# Signal_RX.net
KiCad netlist of a schematic drawn in Altium Designer
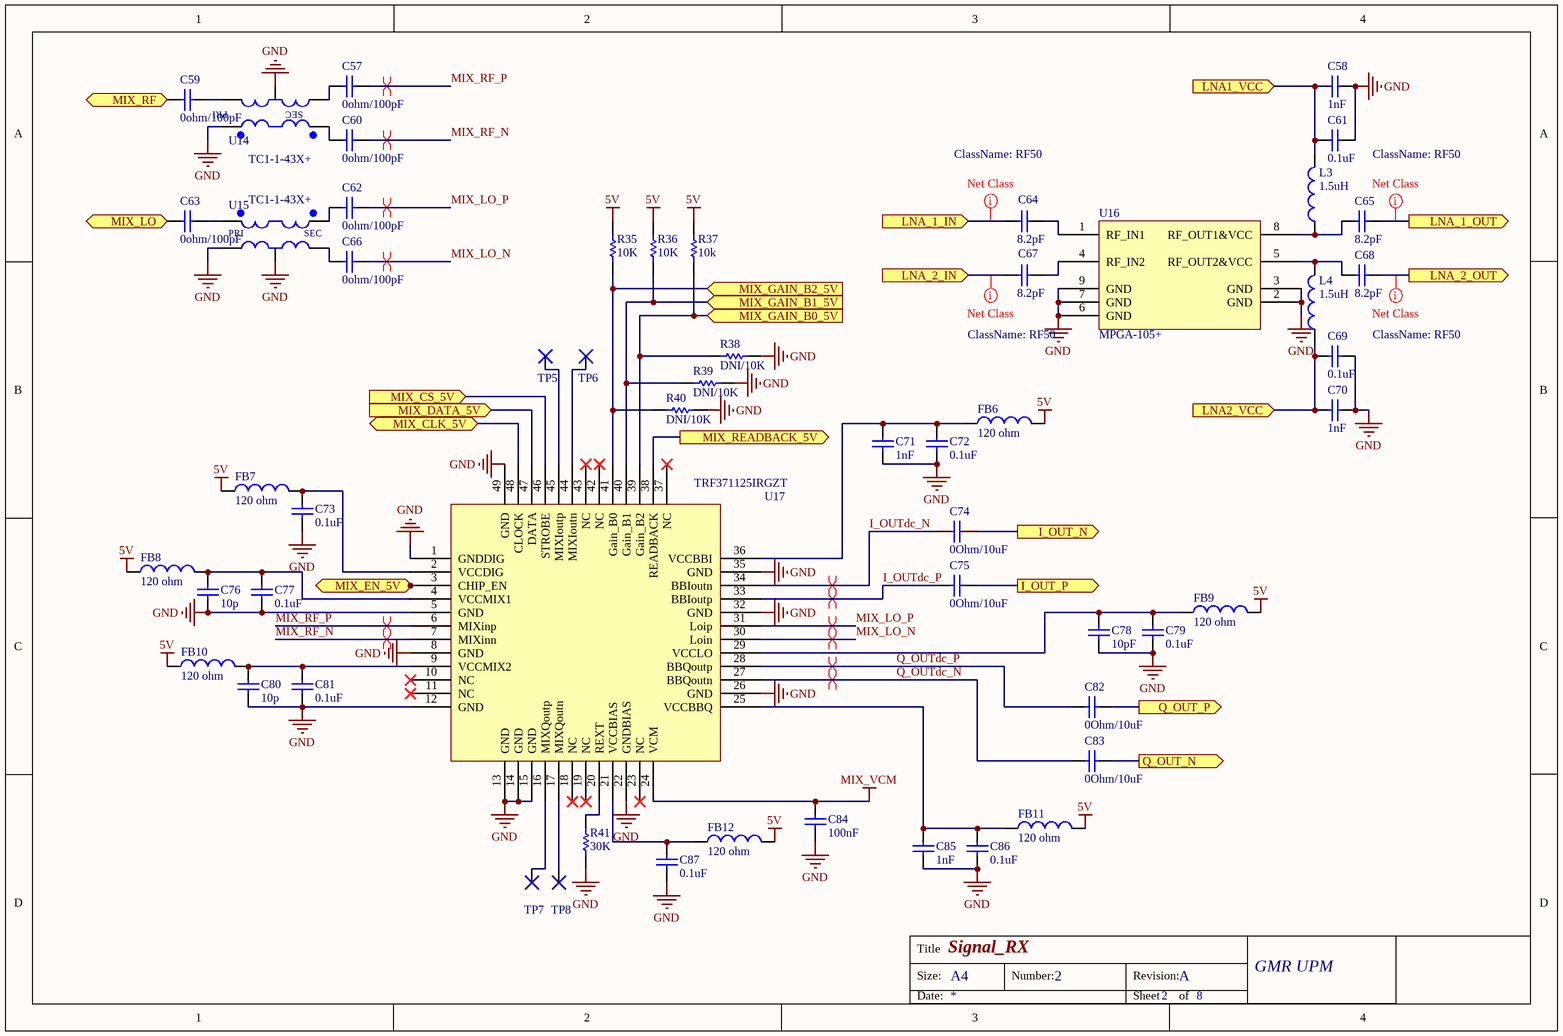
[diagram p0: Signal_RX.SchDoc]

(export (version "E")
  (design (tool "Eeschema 10.0.6"))
  (components
    (comp (ref "C57")
      (value "0ohm/100pF")
      (footprint "0603 Cap")
      (description "CAP CER 16V X7R 0603")
      (fields (field (name "TOLERANCE") "10") (field (name "VOLTAGE") "16"))
      (libsource (lib "Componentes_base") (part "C_0603"))
    )
    (comp (ref "C58")
      (value "1nF")
      (footprint "0603 Cap")
      (description "CAP CER 16V X7R 0603")
      (fields (field (name "TOLERANCE") "10") (field (name "VOLTAGE") "16"))
      (libsource (lib "Componentes_base") (part "C_0603"))
    )
    (comp (ref "C59")
      (value "0ohm/100pF")
      (footprint "0603 Cap")
      (description "CAP CER 16V X7R 0603")
      (fields (field (name "TOLERANCE") "10") (field (name "VOLTAGE") "16"))
      (libsource (lib "Componentes_base") (part "C_0603"))
    )
    (comp (ref "C60")
      (value "0ohm/100pF")
      (footprint "0603 Cap")
      (description "CAP CER 16V X7R 0603")
      (fields (field (name "TOLERANCE") "10") (field (name "VOLTAGE") "16"))
      (libsource (lib "Componentes_base") (part "C_0603"))
    )
    (comp (ref "C61")
      (value "0.1uF")
      (footprint "0603 Cap")
      (description "CAP CER 16V X7R 0603")
      (fields (field (name "TOLERANCE") "10") (field (name "VOLTAGE") "16"))
      (libsource (lib "Componentes_base") (part "C_0603"))
    )
    (comp (ref "C62")
      (value "0ohm/100pF")
      (footprint "0603 Cap")
      (description "CAP CER 16V X7R 0603")
      (fields (field (name "TOLERANCE") "10") (field (name "VOLTAGE") "16"))
      (libsource (lib "Componentes_base") (part "C_0603"))
    )
    (comp (ref "C63")
      (value "0ohm/100pF")
      (footprint "0603 Cap")
      (description "CAP CER 16V X7R 0603")
      (fields (field (name "TOLERANCE") "10") (field (name "VOLTAGE") "16"))
      (libsource (lib "Componentes_base") (part "C_0603"))
    )
    (comp (ref "C64")
      (value "8.2pF")
      (footprint "Chip2PinSM127P600-8N_CAP0402")
      (description "CAP CER 8.2PF 50V NP0 0402")
      (fields
        (field (name "MANUFACTURER") "AVX Corporation")
        (field (name "MANUFACTURER PART NUMBER") "04025A8R2BAT2A")
      )
      (libsource (lib "Componentes_base") (part "04025A8R2BAT2A"))
    )
    (comp (ref "C65")
      (value "8.2pF")
      (footprint "Chip2PinSM127P600-8N_CAP0402")
      (description "CAP CER 8.2PF 50V NP0 0402")
      (fields
        (field (name "MANUFACTURER") "AVX Corporation")
        (field (name "MANUFACTURER PART NUMBER") "04025A8R2BAT2A")
      )
      (libsource (lib "Componentes_base") (part "04025A8R2BAT2A"))
    )
    (comp (ref "C66")
      (value "0ohm/100pF")
      (footprint "0603 Cap")
      (description "CAP CER 16V X7R 0603")
      (fields (field (name "TOLERANCE") "10") (field (name "VOLTAGE") "16"))
      (libsource (lib "Componentes_base") (part "C_0603"))
    )
    (comp (ref "C67")
      (value "8.2pF")
      (footprint "Chip2PinSM127P600-8N_CAP0402")
      (description "CAP CER 8.2PF 50V NP0 0402")
      (fields
        (field (name "MANUFACTURER") "AVX Corporation")
        (field (name "MANUFACTURER PART NUMBER") "04025A8R2BAT2A")
      )
      (libsource (lib "Componentes_base") (part "04025A8R2BAT2A"))
    )
    (comp (ref "C68")
      (value "8.2pF")
      (footprint "Chip2PinSM127P600-8N_CAP0402")
      (description "CAP CER 8.2PF 50V NP0 0402")
      (fields
        (field (name "MANUFACTURER") "AVX Corporation")
        (field (name "MANUFACTURER PART NUMBER") "04025A8R2BAT2A")
      )
      (libsource (lib "Componentes_base") (part "04025A8R2BAT2A"))
    )
    (comp (ref "C69")
      (value "0.1uF")
      (footprint "0603 Cap")
      (description "CAP CER 16V X7R 0603")
      (fields (field (name "TOLERANCE") "10") (field (name "VOLTAGE") "16"))
      (libsource (lib "Componentes_base") (part "C_0603"))
    )
    (comp (ref "C70")
      (value "1nF")
      (footprint "0603 Cap")
      (description "CAP CER 16V X7R 0603")
      (fields (field (name "TOLERANCE") "10") (field (name "VOLTAGE") "16"))
      (libsource (lib "Componentes_base") (part "C_0603"))
    )
    (comp (ref "C71")
      (value "1nF")
      (footprint "0603 Cap")
      (description "CAP CER 16V X7R 0603")
      (fields (field (name "TOLERANCE") "10") (field (name "VOLTAGE") "16"))
      (libsource (lib "Componentes_base") (part "C_0603"))
    )
    (comp (ref "C72")
      (value "0.1uF")
      (footprint "0603 Cap")
      (description "CAP CER 16V X7R 0603")
      (fields (field (name "TOLERANCE") "10") (field (name "VOLTAGE") "16"))
      (libsource (lib "Componentes_base") (part "C_0603"))
    )
    (comp (ref "C73")
      (value "0.1uF")
      (footprint "0603 Cap")
      (description "CAP CER 16V X7R 0603")
      (fields (field (name "TOLERANCE") "10") (field (name "VOLTAGE") "16"))
      (libsource (lib "Componentes_base") (part "C_0603"))
    )
    (comp (ref "C74")
      (value "0Ohm/10uF")
      (footprint "0603 Cap")
      (description "CAP CER 16V X7R 0603")
      (fields (field (name "TOLERANCE") "10") (field (name "VOLTAGE") "16"))
      (libsource (lib "Componentes_base") (part "C_0603"))
    )
    (comp (ref "C75")
      (value "0Ohm/10uF")
      (footprint "0603 Cap")
      (description "CAP CER 16V X7R 0603")
      (fields (field (name "TOLERANCE") "10") (field (name "VOLTAGE") "16"))
      (libsource (lib "Componentes_base") (part "C_0603"))
    )
    (comp (ref "C76")
      (value "10p")
      (footprint "0603 Cap")
      (description "CAP CER 16V X7R 0603")
      (fields (field (name "TOLERANCE") "10") (field (name "VOLTAGE") "16"))
      (libsource (lib "Componentes_base") (part "C_0603"))
    )
    (comp (ref "C77")
      (value "0.1uF")
      (footprint "0603 Cap")
      (description "CAP CER 16V X7R 0603")
      (fields (field (name "TOLERANCE") "10") (field (name "VOLTAGE") "16"))
      (libsource (lib "Componentes_base") (part "C_0603"))
    )
    (comp (ref "C78")
      (value "10pF")
      (footprint "0603 Cap")
      (description "CAP CER 16V X7R 0603")
      (fields (field (name "TOLERANCE") "10") (field (name "VOLTAGE") "16"))
      (libsource (lib "Componentes_base") (part "C_0603"))
    )
    (comp (ref "C79")
      (value "0.1uF")
      (footprint "0603 Cap")
      (description "CAP CER 16V X7R 0603")
      (fields (field (name "TOLERANCE") "10") (field (name "VOLTAGE") "16"))
      (libsource (lib "Componentes_base") (part "C_0603"))
    )
    (comp (ref "C80")
      (value "10p")
      (footprint "0603 Cap")
      (description "CAP CER 16V X7R 0603")
      (fields (field (name "TOLERANCE") "10") (field (name "VOLTAGE") "16"))
      (libsource (lib "Componentes_base") (part "C_0603"))
    )
    (comp (ref "C81")
      (value "0.1uF")
      (footprint "0603 Cap")
      (description "CAP CER 16V X7R 0603")
      (fields (field (name "TOLERANCE") "10") (field (name "VOLTAGE") "16"))
      (libsource (lib "Componentes_base") (part "C_0603"))
    )
    (comp (ref "C82")
      (value "0Ohm/10uF")
      (footprint "0603 Cap")
      (description "CAP CER 16V X7R 0603")
      (fields (field (name "TOLERANCE") "10") (field (name "VOLTAGE") "16"))
      (libsource (lib "Componentes_base") (part "C_0603"))
    )
    (comp (ref "C83")
      (value "0Ohm/10uF")
      (footprint "0603 Cap")
      (description "CAP CER 16V X7R 0603")
      (fields (field (name "TOLERANCE") "10") (field (name "VOLTAGE") "16"))
      (libsource (lib "Componentes_base") (part "C_0603"))
    )
    (comp (ref "C84")
      (value "100nF")
      (footprint "0603 Cap")
      (description "CAP CER 16V X7R 0603")
      (fields (field (name "TOLERANCE") "10") (field (name "VOLTAGE") "16"))
      (libsource (lib "Componentes_base") (part "C_0603"))
    )
    (comp (ref "C85")
      (value "1nF")
      (footprint "0603 Cap")
      (description "CAP CER 16V X7R 0603")
      (fields (field (name "TOLERANCE") "10") (field (name "VOLTAGE") "16"))
      (libsource (lib "Componentes_base") (part "C_0603"))
    )
    (comp (ref "C86")
      (value "0.1uF")
      (footprint "0603 Cap")
      (description "CAP CER 16V X7R 0603")
      (fields (field (name "TOLERANCE") "10") (field (name "VOLTAGE") "16"))
      (libsource (lib "Componentes_base") (part "C_0603"))
    )
    (comp (ref "C87")
      (value "0.1uF")
      (footprint "0603 Cap")
      (description "CAP CER 16V X7R 0603")
      (fields (field (name "TOLERANCE") "10") (field (name "VOLTAGE") "16"))
      (libsource (lib "Componentes_base") (part "C_0603"))
    )
    (comp (ref "FB6")
      (value "120 ohm")
      (footprint "INDC1608X08L")
      (description "FERRITE BEAD 120 OHM 0603 1LN")
      (fields
        (field (name "MANUFACTURER") "Murata Electronics North America")
        (field (name "MANUFACTURER PART NUMBER") "BLM18PG121SN1D")
      )
      (libsource (lib "Componentes_base") (part "BLM18PG121SN1D"))
    )
    (comp (ref "FB7")
      (value "120 ohm")
      (footprint "INDC1608X08L")
      (description "FERRITE BEAD 120 OHM 0603 1LN")
      (fields
        (field (name "MANUFACTURER") "Murata Electronics North America")
        (field (name "MANUFACTURER PART NUMBER") "BLM18PG121SN1D")
      )
      (libsource (lib "") (part "BLM18PG121SN1D_1"))
    )
    (comp (ref "FB8")
      (value "120 ohm")
      (footprint "INDC1608X08L")
      (description "FERRITE BEAD 120 OHM 0603 1LN")
      (fields
        (field (name "MANUFACTURER") "Murata Electronics North America")
        (field (name "MANUFACTURER PART NUMBER") "BLM18PG121SN1D")
      )
      (libsource (lib "") (part "BLM18PG121SN1D_1"))
    )
    (comp (ref "FB9")
      (value "120 ohm")
      (footprint "INDC1608X08L")
      (description "FERRITE BEAD 120 OHM 0603 1LN")
      (fields
        (field (name "MANUFACTURER") "Murata Electronics North America")
        (field (name "MANUFACTURER PART NUMBER") "BLM18PG121SN1D")
      )
      (libsource (lib "Componentes_base") (part "BLM18PG121SN1D"))
    )
    (comp (ref "FB10")
      (value "120 ohm")
      (footprint "INDC1608X08L")
      (description "FERRITE BEAD 120 OHM 0603 1LN")
      (fields
        (field (name "MANUFACTURER") "Murata Electronics North America")
        (field (name "MANUFACTURER PART NUMBER") "BLM18PG121SN1D")
      )
      (libsource (lib "") (part "BLM18PG121SN1D_1"))
    )
    (comp (ref "FB11")
      (value "120 ohm")
      (footprint "INDC1608X08L")
      (description "FERRITE BEAD 120 OHM 0603 1LN")
      (fields
        (field (name "MANUFACTURER") "Murata Electronics North America")
        (field (name "MANUFACTURER PART NUMBER") "BLM18PG121SN1D")
      )
      (libsource (lib "Componentes_base") (part "BLM18PG121SN1D"))
    )
    (comp (ref "FB12")
      (value "120 ohm")
      (footprint "INDC1608X08L")
      (description "FERRITE BEAD 120 OHM 0603 1LN")
      (fields
        (field (name "MANUFACTURER") "Murata Electronics North America")
        (field (name "MANUFACTURER PART NUMBER") "BLM18PG121SN1D")
      )
      (libsource (lib "Componentes_base") (part "BLM18PG121SN1D"))
    )
    (comp (ref "L3")
      (value "1.5uH")
      (footprint "INDC1008X07L")
      (description "FIXED IND 1.5UH 630MA 760 MOHM")
      (fields
        (field (name "MANUFACTURER") "Abracon LLC")
        (field (name "MANUFACTURER PART NUMBER") "AISC-1008F-1R5G-T")
      )
      (libsource (lib "") (part "AISC-1008F-1R5G-T_1"))
    )
    (comp (ref "L4")
      (value "1.5uH")
      (footprint "INDC1008X07L")
      (description "FIXED IND 1.5UH 630MA 760 MOHM")
      (fields
        (field (name "MANUFACTURER") "Abracon LLC")
        (field (name "MANUFACTURER PART NUMBER") "AISC-1008F-1R5G-T")
      )
      (libsource (lib "Componentes_base") (part "AISC-1008F-1R5G-T"))
    )
    (comp (ref "R35")
      (value "10K")
      (footprint "0603 Res")
      (description "SMD Resistor, 1%, 0.1W, 0603")
      (fields (field (name "TOLERANCE") "1"))
      (libsource (lib "Componentes_base") (part "R_0603"))
    )
    (comp (ref "R36")
      (value "10K")
      (footprint "0603 Res")
      (description "SMD Resistor, 1%, 0.1W, 0603")
      (fields (field (name "TOLERANCE") "1"))
      (libsource (lib "Componentes_base") (part "R_0603"))
    )
    (comp (ref "R37")
      (value "10k")
      (footprint "0603 Res")
      (description "SMD Resistor, 1%, 0.1W, 0603")
      (fields (field (name "TOLERANCE") "1"))
      (libsource (lib "Componentes_base") (part "R_0603"))
    )
    (comp (ref "R38")
      (value "DNI/10K")
      (footprint "0603 Res")
      (description "SMD Resistor, 1%, 0.1W, 0603")
      (fields (field (name "TOLERANCE") "1"))
      (libsource (lib "Componentes_base") (part "R_0603"))
    )
    (comp (ref "R39")
      (value "DNI/10K")
      (footprint "0603 Res")
      (description "SMD Resistor, 1%, 0.1W, 0603")
      (fields (field (name "TOLERANCE") "1"))
      (libsource (lib "Componentes_base") (part "R_0603"))
    )
    (comp (ref "R40")
      (value "DNI/10K")
      (footprint "0603 Res")
      (description "SMD Resistor, 1%, 0.1W, 0603")
      (fields (field (name "TOLERANCE") "1"))
      (libsource (lib "Componentes_base") (part "R_0603"))
    )
    (comp (ref "R41")
      (value "30K")
      (footprint "0603 Res")
      (description "SMD Resistor, 1%, 0.1W, 0603")
      (fields (field (name "TOLERANCE") "1"))
      (libsource (lib "Componentes_base") (part "R_0603"))
    )
    (comp (ref "TP5")
      (value "TEST_POINT_PIN")
      (footprint "TESTPOINT")
      (description "Test point for single pin")
      (libsource (lib "Componentes_base") (part "TEST_POINT_PIN"))
    )
    (comp (ref "TP6")
      (value "TEST_POINT_PIN")
      (footprint "TESTPOINT")
      (description "Test point for single pin")
      (libsource (lib "Componentes_base") (part "TEST_POINT_PIN"))
    )
    (comp (ref "TP7")
      (value "TEST_POINT_PIN")
      (footprint "TESTPOINT")
      (description "Test point for single pin")
      (libsource (lib "Componentes_base") (part "TEST_POINT_PIN"))
    )
    (comp (ref "TP8")
      (value "TEST_POINT_PIN")
      (footprint "TESTPOINT")
      (description "Test point for single pin")
      (libsource (lib "Componentes_base") (part "TEST_POINT_PIN"))
    )
    (comp (ref "U14")
      (value "TC1-1-43X+")
      (footprint "AT1521")
      (description "SMD RF Transformer")
      (fields (field (name "MANUFACTURER") "Minicircuits"))
      (libsource (lib "") (part "TC1-1-43X+_1"))
    )
    (comp (ref "U15")
      (value "TC1-1-43X+")
      (footprint "AT1521")
      (description "SMD RF Transformer")
      (fields (field (name "MANUFACTURER") "Minicircuits"))
      (libsource (lib "Schlib1") (part "TC1-1-43X+"))
    )
    (comp (ref "U16")
      (value "MPGA-105+")
      (footprint "DL1020_recomendedValues")
      (description "Dual Matched MMIC Ampli er")
      (fields (field (name "MANUFACTURER") "Minicircuits"))
      (libsource (lib "Schlib1") (part "MPGA-105+"))
    )
    (comp (ref "U17")
      (value "TRF371125IRGZT")
      (footprint "QFN50P700X700X100_HS-49M")
      (description "IC IQ DEMODULATOR W/PGA 48VQFN")
      (fields (field (name "MANUFACTURER") "Texas Instruments"))
      (libsource (lib "Schlib1") (part "TRF371125IRGZT"))
    )
  )
  (nets
    (net (code "1") (name "/I_OUT_N") (class "Default")
      (node (ref "C74") (pin "1") (pinfunction "1_1") (pintype "passive"))
    )
    (net (code "2") (name "/I_OUT_P") (class "Default")
      (node (ref "C75") (pin "1") (pinfunction "1_1") (pintype "passive"))
    )
    (net (code "3") (name "/I_OUTdc_N") (class "Default")
      (node (ref "C74") (pin "2") (pinfunction "2_2") (pintype "passive"))
      (node (ref "U17") (pin "34") (pinfunction "BBIoutn_34") (pintype "passive"))
    )
    (net (code "4") (name "/I_OUTdc_P") (class "Default")
      (node (ref "C75") (pin "2") (pinfunction "2_2") (pintype "passive"))
      (node (ref "U17") (pin "33") (pinfunction "BBIoutp_33") (pintype "passive"))
    )
    (net (code "5") (name "/LNA1_VCC") (class "Default")
      (node (ref "C58") (pin "2") (pinfunction "2_2") (pintype "passive"))
      (node (ref "C61") (pin "2") (pinfunction "2_2") (pintype "passive"))
      (node (ref "L3") (pin "2") (pinfunction "2_2") (pintype "passive"))
    )
    (net (code "6") (name "/LNA2_VCC") (class "Default")
      (node (ref "C69") (pin "1") (pinfunction "1_1") (pintype "passive"))
      (node (ref "C70") (pin "1") (pinfunction "1_1") (pintype "passive"))
      (node (ref "L4") (pin "2") (pinfunction "2_2") (pintype "passive"))
    )
    (net (code "7") (name "/LNA_1_IN") (class "Default")
      (node (ref "C64") (pin "1") (pinfunction "1_1") (pintype "passive"))
    )
    (net (code "8") (name "/LNA_1_OUT") (class "Default")
      (node (ref "C65") (pin "2") (pinfunction "2_2") (pintype "passive"))
    )
    (net (code "9") (name "/LNA_2_IN") (class "Default")
      (node (ref "C67") (pin "1") (pinfunction "1_1") (pintype "passive"))
    )
    (net (code "10") (name "/LNA_2_OUT") (class "Default")
      (node (ref "C68") (pin "2") (pinfunction "2_2") (pintype "passive"))
    )
    (net (code "11") (name "/MIX_CLK_5V") (class "Default")
      (node (ref "U17") (pin "48") (pinfunction "CLOCK_48") (pintype "passive"))
    )
    (net (code "12") (name "/MIX_CS_5V") (class "Default")
      (node (ref "U17") (pin "46") (pinfunction "STROBE_46") (pintype "passive"))
    )
    (net (code "13") (name "/MIX_DATA_5V") (class "Default")
      (node (ref "U17") (pin "47") (pinfunction "DATA_47") (pintype "passive"))
    )
    (net (code "15") (name "/MIX_GAIN_B0_5V") (class "Default")
      (node (ref "R37") (pin "1") (pinfunction "1_1") (pintype "passive"))
      (node (ref "R38") (pin "2") (pinfunction "2_2") (pintype "passive"))
      (node (ref "U17") (pin "39") (pinfunction "Gain_B2_39") (pintype "passive"))
    )
    (net (code "16") (name "/MIX_GAIN_B1_5V") (class "Default")
      (node (ref "R36") (pin "1") (pinfunction "1_1") (pintype "passive"))
      (node (ref "R39") (pin "2") (pinfunction "2_2") (pintype "passive"))
      (node (ref "U17") (pin "40") (pinfunction "Gain_B1_40") (pintype "passive"))
    )
    (net (code "17") (name "/MIX_GAIN_B2_5V") (class "Default")
      (node (ref "R35") (pin "1") (pinfunction "1_1") (pintype "passive"))
      (node (ref "R40") (pin "2") (pinfunction "2_2") (pintype "passive"))
      (node (ref "U17") (pin "41") (pinfunction "Gain_B0_41") (pintype "passive"))
    )
    (net (code "18") (name "/MIX_LO") (class "Default")
      (node (ref "C63") (pin "1") (pinfunction "1_1") (pintype "passive"))
    )
    (net (code "19") (name "/MIX_LO_N") (class "Default")
      (node (ref "C66") (pin "2") (pinfunction "2_2") (pintype "passive"))
      (node (ref "U17") (pin "30") (pinfunction "Loin_30") (pintype "passive"))
    )
    (net (code "20") (name "/MIX_LO_P") (class "Default")
      (node (ref "C62") (pin "2") (pinfunction "2_2") (pintype "passive"))
      (node (ref "U17") (pin "31") (pinfunction "Loip_31") (pintype "passive"))
    )
    (net (code "21") (name "/MIX_READBACK_5V") (class "Default")
      (node (ref "U17") (pin "38") (pinfunction "READBACK_38") (pintype "passive"))
    )
    (net (code "22") (name "/MIX_RF") (class "Default")
      (node (ref "C59") (pin "1") (pinfunction "1_1") (pintype "passive"))
    )
    (net (code "23") (name "/MIX_RF_N") (class "Default")
      (node (ref "C60") (pin "2") (pinfunction "2_2") (pintype "passive"))
      (node (ref "U17") (pin "7") (pinfunction "MIXinn_7") (pintype "passive"))
    )
    (net (code "24") (name "/MIX_RF_P") (class "Default")
      (node (ref "C57") (pin "2") (pinfunction "2_2") (pintype "passive"))
      (node (ref "U17") (pin "6") (pinfunction "MIXinp_6") (pintype "passive"))
    )
    (net (code "25") (name "/Q_OUT_N") (class "Default")
      (node (ref "C83") (pin "1") (pinfunction "1_1") (pintype "passive"))
    )
    (net (code "26") (name "/Q_OUT_P") (class "Default")
      (node (ref "C82") (pin "1") (pinfunction "1_1") (pintype "passive"))
    )
    (net (code "27") (name "/Q_OUTdc_N") (class "Default")
      (node (ref "C83") (pin "2") (pinfunction "2_2") (pintype "passive"))
      (node (ref "U17") (pin "27") (pinfunction "BBQoutn_27") (pintype "passive"))
    )
    (net (code "28") (name "/Q_OUTdc_P") (class "Default")
      (node (ref "C82") (pin "2") (pinfunction "2_2") (pintype "passive"))
      (node (ref "U17") (pin "28") (pinfunction "BBQoutp_28") (pintype "passive"))
    )
    (net (code "29") (name "5V") (class "Default")
      (node (ref "FB10") (pin "1") (pinfunction "1_1") (pintype "passive"))
      (node (ref "FB11") (pin "1") (pinfunction "1_1") (pintype "passive"))
      (node (ref "FB12") (pin "1") (pinfunction "1_1") (pintype "passive"))
      (node (ref "FB6") (pin "1") (pinfunction "1_1") (pintype "passive"))
      (node (ref "FB7") (pin "1") (pinfunction "1_1") (pintype "passive"))
      (node (ref "FB8") (pin "1") (pinfunction "1_1") (pintype "passive"))
      (node (ref "FB9") (pin "1") (pinfunction "1_1") (pintype "passive"))
      (node (ref "R35") (pin "2") (pinfunction "2_2") (pintype "passive"))
      (node (ref "R36") (pin "2") (pinfunction "2_2") (pintype "passive"))
      (node (ref "R37") (pin "2") (pinfunction "2_2") (pintype "passive"))
    )
    (net (code "30") (name "GND") (class "Default")
      (node (ref "C58") (pin "1") (pinfunction "1_1") (pintype "passive"))
      (node (ref "C61") (pin "1") (pinfunction "1_1") (pintype "passive"))
      (node (ref "C69") (pin "2") (pinfunction "2_2") (pintype "passive"))
      (node (ref "C70") (pin "2") (pinfunction "2_2") (pintype "passive"))
      (node (ref "C71") (pin "2") (pinfunction "2_2") (pintype "passive"))
      (node (ref "C72") (pin "2") (pinfunction "2_2") (pintype "passive"))
      (node (ref "C73") (pin "1") (pinfunction "1_1") (pintype "passive"))
      (node (ref "C76") (pin "1") (pinfunction "1_1") (pintype "passive"))
      (node (ref "C77") (pin "1") (pinfunction "1_1") (pintype "passive"))
      (node (ref "C78") (pin "2") (pinfunction "2_2") (pintype "passive"))
      (node (ref "C79") (pin "2") (pinfunction "2_2") (pintype "passive"))
      (node (ref "C80") (pin "1") (pinfunction "1_1") (pintype "passive"))
      (node (ref "C81") (pin "1") (pinfunction "1_1") (pintype "passive"))
      (node (ref "C84") (pin "2") (pinfunction "2_2") (pintype "passive"))
      (node (ref "C85") (pin "2") (pinfunction "2_2") (pintype "passive"))
      (node (ref "C86") (pin "2") (pinfunction "2_2") (pintype "passive"))
      (node (ref "C87") (pin "2") (pinfunction "2_2") (pintype "passive"))
      (node (ref "R38") (pin "1") (pinfunction "1_1") (pintype "passive"))
      (node (ref "R39") (pin "1") (pinfunction "1_1") (pintype "passive"))
      (node (ref "R40") (pin "1") (pinfunction "1_1") (pintype "passive"))
      (node (ref "R41") (pin "1") (pinfunction "1_1") (pintype "passive"))
      (node (ref "U14") (pin "2") (pinfunction "NC_2") (pintype "passive"))
      (node (ref "U14") (pin "6") (pinfunction "6_6") (pintype "passive"))
      (node (ref "U15") (pin "2") (pinfunction "NC_2") (pintype "passive"))
      (node (ref "U15") (pin "4") (pinfunction "4_4") (pintype "passive"))
      (node (ref "U16") (pin "2") (pinfunction "GND_2") (pintype "power_in"))
      (node (ref "U16") (pin "3") (pinfunction "GND_3") (pintype "power_in"))
      (node (ref "U16") (pin "6") (pinfunction "GND_6") (pintype "power_in"))
      (node (ref "U16") (pin "7") (pinfunction "GND_7") (pintype "power_in"))
      (node (ref "U16") (pin "9") (pinfunction "GND_9") (pintype "power_in"))
      (node (ref "U17") (pin "1") (pinfunction "GNDDIG_1") (pintype "power_in"))
      (node (ref "U17") (pin "12") (pinfunction "GND_12") (pintype "power_in"))
      (node (ref "U17") (pin "13") (pinfunction "GND_13") (pintype "power_in"))
      (node (ref "U17") (pin "14") (pinfunction "GND_14") (pintype "power_in"))
      (node (ref "U17") (pin "15") (pinfunction "GND_15") (pintype "power_in"))
      (node (ref "U17") (pin "22") (pinfunction "GNDBIAS_22") (pintype "power_in"))
      (node (ref "U17") (pin "26") (pinfunction "GND_26") (pintype "power_in"))
      (node (ref "U17") (pin "32") (pinfunction "GND_32") (pintype "power_in"))
      (node (ref "U17") (pin "35") (pinfunction "GND_35") (pintype "power_in"))
      (node (ref "U17") (pin "49") (pinfunction "GND_49") (pintype "power_in"))
      (node (ref "U17") (pin "5") (pinfunction "GND_5") (pintype "power_in"))
      (node (ref "U17") (pin "8") (pinfunction "GND_8") (pintype "power_in"))
    )
    (net (code "31") (name "MIX_VCM") (class "Default")
      (node (ref "C84") (pin "1") (pinfunction "1_1") (pintype "passive"))
      (node (ref "U17") (pin "24") (pinfunction "VCM_24") (pintype "passive"))
    )
    (net (code "32") (name "Net-(C57-Pad1)") (class "Default")
      (node (ref "C57") (pin "1") (pinfunction "1_1") (pintype "passive"))
      (node (ref "U14") (pin "3") (pinfunction "3_3") (pintype "passive"))
    )
    (net (code "33") (name "Net-(C59-Pad2)") (class "Default")
      (node (ref "C59") (pin "2") (pinfunction "2_2") (pintype "passive"))
      (node (ref "U14") (pin "4") (pinfunction "4_4") (pintype "passive"))
    )
    (net (code "34") (name "Net-(C60-Pad1)") (class "Default")
      (node (ref "C60") (pin "1") (pinfunction "1_1") (pintype "passive"))
      (node (ref "U14") (pin "1") (pinfunction "1_1") (pintype "passive"))
    )
    (net (code "35") (name "Net-(C62-Pad1)") (class "Default")
      (node (ref "C62") (pin "1") (pinfunction "1_1") (pintype "passive"))
      (node (ref "U15") (pin "1") (pinfunction "1_1") (pintype "passive"))
    )
    (net (code "36") (name "Net-(C63-Pad2)") (class "Default")
      (node (ref "C63") (pin "2") (pinfunction "2_2") (pintype "passive"))
      (node (ref "U15") (pin "6") (pinfunction "6_6") (pintype "passive"))
    )
    (net (code "37") (name "Net-(C66-Pad1)") (class "Default")
      (node (ref "C66") (pin "1") (pinfunction "1_1") (pintype "passive"))
      (node (ref "U15") (pin "3") (pinfunction "3_3") (pintype "passive"))
    )
    (net (code "38") (name "Net-(U16-RF_IN1)") (class "Default")
      (node (ref "C64") (pin "2") (pinfunction "2_2") (pintype "passive"))
      (node (ref "U16") (pin "1") (pinfunction "RF_IN1_1") (pintype "passive"))
    )
    (net (code "39") (name "Net-(U16-RF_IN2)") (class "Default")
      (node (ref "C67") (pin "2") (pinfunction "2_2") (pintype "passive"))
      (node (ref "U16") (pin "4") (pinfunction "RF_IN2_4") (pintype "passive"))
    )
    (net (code "40") (name "Net-(U16-RF_OUT1&VCC)") (class "Default")
      (node (ref "C65") (pin "1") (pinfunction "1_1") (pintype "passive"))
      (node (ref "L3") (pin "1") (pinfunction "1_1") (pintype "passive"))
      (node (ref "U16") (pin "8") (pinfunction "RF_OUT1&VCC_8") (pintype "passive"))
    )
    (net (code "41") (name "Net-(U16-RF_OUT2&VCC)") (class "Default")
      (node (ref "C68") (pin "1") (pinfunction "1_1") (pintype "passive"))
      (node (ref "L4") (pin "1") (pinfunction "1_1") (pintype "passive"))
      (node (ref "U16") (pin "5") (pinfunction "RF_OUT2&VCC_5") (pintype "passive"))
    )
    (net (code "42") (name "Net-(U17-MIXIoutn)") (class "Default")
      (node (ref "TP6") (pin "1") (pinfunction "1_1") (pintype "passive"))
      (node (ref "U17") (pin "44") (pinfunction "MIXIoutn_44") (pintype "passive"))
    )
    (net (code "43") (name "Net-(U17-MIXIoutp)") (class "Default")
      (node (ref "TP5") (pin "1") (pinfunction "1_1") (pintype "passive"))
      (node (ref "U17") (pin "45") (pinfunction "MIXIoutp_45") (pintype "passive"))
    )
    (net (code "44") (name "Net-(U17-MIXQoutn)") (class "Default")
      (node (ref "TP8") (pin "1") (pinfunction "1_1") (pintype "passive"))
      (node (ref "U17") (pin "17") (pinfunction "MIXQoutn_17") (pintype "passive"))
    )
    (net (code "45") (name "Net-(U17-MIXQoutp)") (class "Default")
      (node (ref "TP7") (pin "1") (pinfunction "1_1") (pintype "passive"))
      (node (ref "U17") (pin "16") (pinfunction "MIXQoutp_16") (pintype "passive"))
    )
    (net (code "46") (name "Net-(U17-REXT)") (class "Default")
      (node (ref "R41") (pin "2") (pinfunction "2_2") (pintype "passive"))
      (node (ref "U17") (pin "20") (pinfunction "REXT_20") (pintype "passive"))
    )
    (net (code "47") (name "Net-(U17-VCCBBI)") (class "Default")
      (node (ref "C71") (pin "1") (pinfunction "1_1") (pintype "passive"))
      (node (ref "C72") (pin "1") (pinfunction "1_1") (pintype "passive"))
      (node (ref "FB6") (pin "2") (pinfunction "2_2") (pintype "passive"))
      (node (ref "U17") (pin "36") (pinfunction "VCCBBI_36") (pintype "power_in"))
    )
    (net (code "48") (name "Net-(U17-VCCBBQ)") (class "Default")
      (node (ref "C85") (pin "1") (pinfunction "1_1") (pintype "passive"))
      (node (ref "C86") (pin "1") (pinfunction "1_1") (pintype "passive"))
      (node (ref "FB11") (pin "2") (pinfunction "2_2") (pintype "passive"))
      (node (ref "U17") (pin "25") (pinfunction "VCCBBQ_25") (pintype "power_in"))
    )
    (net (code "49") (name "Net-(U17-VCCBIAS)") (class "Default")
      (node (ref "C87") (pin "1") (pinfunction "1_1") (pintype "passive"))
      (node (ref "FB12") (pin "2") (pinfunction "2_2") (pintype "passive"))
      (node (ref "U17") (pin "21") (pinfunction "VCCBIAS_21") (pintype "power_in"))
    )
    (net (code "50") (name "Net-(U17-VCCDIG)") (class "Default")
      (node (ref "C73") (pin "2") (pinfunction "2_2") (pintype "passive"))
      (node (ref "FB7") (pin "2") (pinfunction "2_2") (pintype "passive"))
      (node (ref "U17") (pin "2") (pinfunction "VCCDIG_2") (pintype "power_in"))
    )
    (net (code "51") (name "Net-(U17-VCCLO)") (class "Default")
      (node (ref "C78") (pin "1") (pinfunction "1_1") (pintype "passive"))
      (node (ref "C79") (pin "1") (pinfunction "1_1") (pintype "passive"))
      (node (ref "FB9") (pin "2") (pinfunction "2_2") (pintype "passive"))
      (node (ref "U17") (pin "29") (pinfunction "VCCLO_29") (pintype "power_in"))
    )
    (net (code "52") (name "Net-(U17-VCCMIX1)") (class "Default")
      (node (ref "C76") (pin "2") (pinfunction "2_2") (pintype "passive"))
      (node (ref "C77") (pin "2") (pinfunction "2_2") (pintype "passive"))
      (node (ref "FB8") (pin "2") (pinfunction "2_2") (pintype "passive"))
      (node (ref "U17") (pin "4") (pinfunction "VCCMIX1_4") (pintype "power_in"))
    )
    (net (code "53") (name "Net-(U17-VCCMIX2)") (class "Default")
      (node (ref "C80") (pin "2") (pinfunction "2_2") (pintype "passive"))
      (node (ref "C81") (pin "2") (pinfunction "2_2") (pintype "passive"))
      (node (ref "FB10") (pin "2") (pinfunction "2_2") (pintype "passive"))
      (node (ref "U17") (pin "9") (pinfunction "VCCMIX2_9") (pintype "power_in"))
    )
    (net (code "54") (name "unconnected-(U17-CHIP_EN-Pad3)") (class "Default")
      (node (ref "U17") (pin "3") (pinfunction "CHIP_EN_3") (pintype "passive"))
    )
    (net (code "55") (name "unconnected-(U17-NC-Pad10)") (class "Default")
      (node (ref "U17") (pin "10") (pinfunction "NC_10") (pintype "passive+no_connect"))
    )
    (net (code "56") (name "unconnected-(U17-NC-Pad11)") (class "Default")
      (node (ref "U17") (pin "11") (pinfunction "NC_11") (pintype "passive+no_connect"))
    )
    (net (code "57") (name "unconnected-(U17-NC-Pad18)") (class "Default")
      (node (ref "U17") (pin "18") (pinfunction "NC_18") (pintype "passive+no_connect"))
    )
    (net (code "58") (name "unconnected-(U17-NC-Pad19)") (class "Default")
      (node (ref "U17") (pin "19") (pinfunction "NC_19") (pintype "passive+no_connect"))
    )
    (net (code "59") (name "unconnected-(U17-NC-Pad23)") (class "Default")
      (node (ref "U17") (pin "23") (pinfunction "NC_23") (pintype "passive+no_connect"))
    )
    (net (code "60") (name "unconnected-(U17-NC-Pad37)") (class "Default")
      (node (ref "U17") (pin "37") (pinfunction "NC_37") (pintype "passive+no_connect"))
    )
    (net (code "61") (name "unconnected-(U17-NC-Pad42)") (class "Default")
      (node (ref "U17") (pin "42") (pinfunction "NC_42") (pintype "passive+no_connect"))
    )
    (net (code "62") (name "unconnected-(U17-NC-Pad43)") (class "Default")
      (node (ref "U17") (pin "43") (pinfunction "NC_43") (pintype "passive+no_connect"))
    )
  )
)
